# Summits7Beta_Sch.net
KiCad netlist of a schematic drawn in Altium Designer
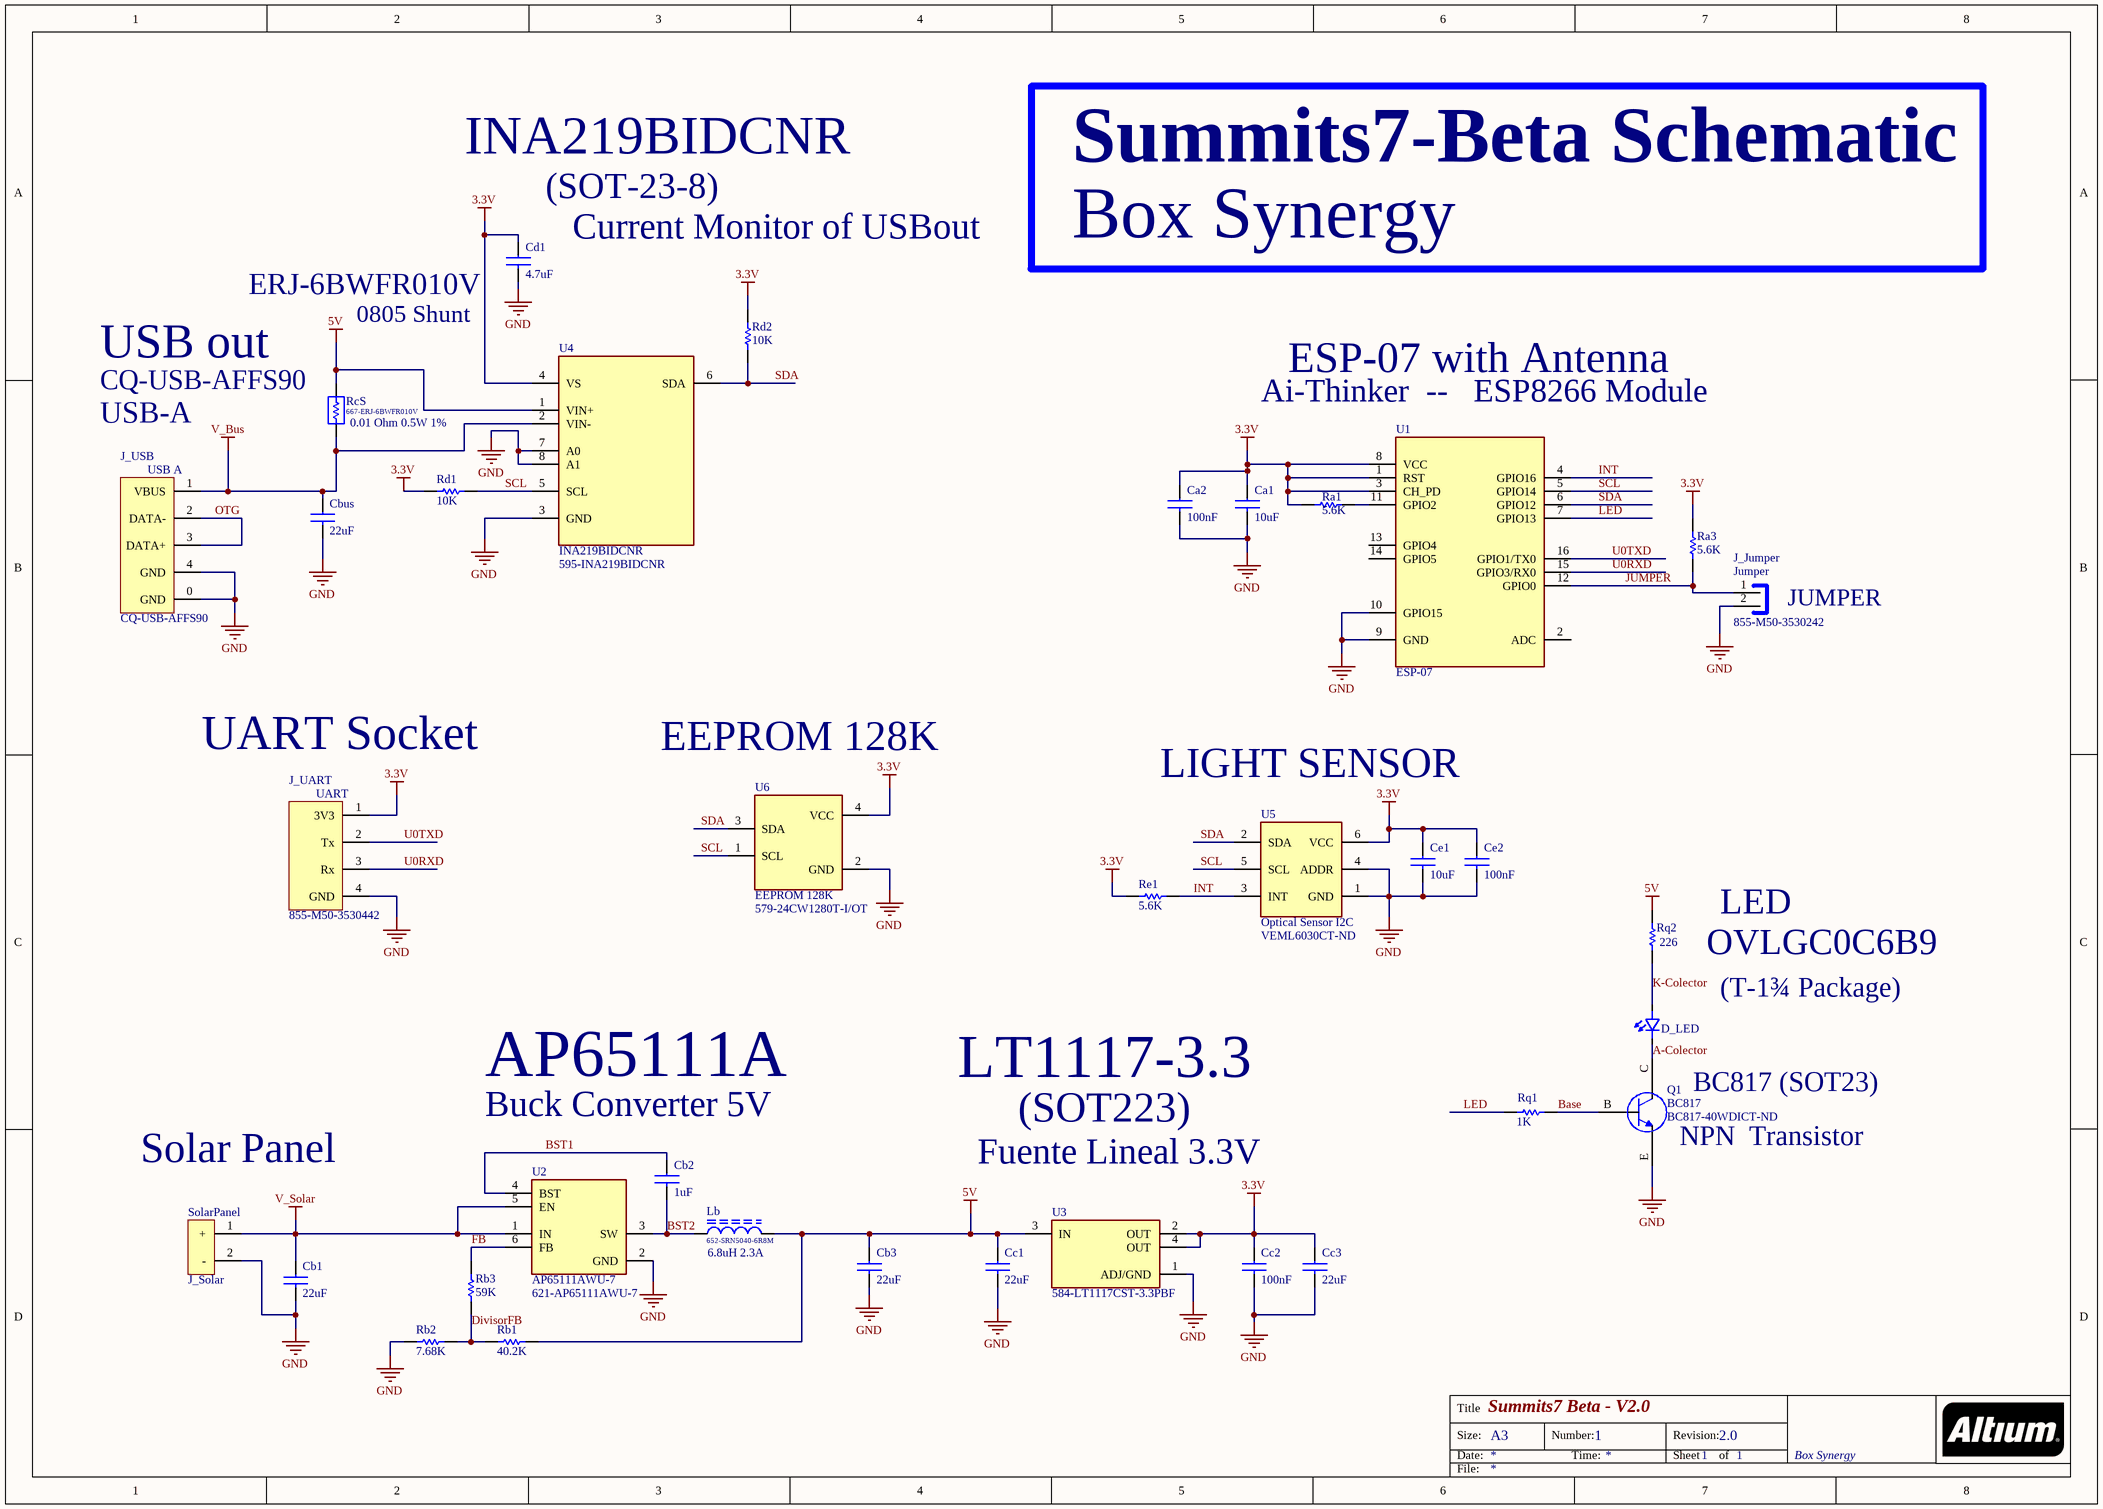
[diagram p0: Summits7Beta_Sch.SchDoc]

(export (version "E")
  (design (tool "Eeschema 10.0.6"))
  (components
    (comp (ref "Ca1")
      (value "10uF")
      (footprint "CAP_0603")
      (description "Capac Ceramic SMD")
      (libsource (lib "Summits7Beta_LIB_Pasivos_Sch") (part "Cap_0603_Ceramic"))
    )
    (comp (ref "Ca2")
      (value "100nF")
      (footprint "CAP_0603")
      (description "Capac Ceramic SMD")
      (libsource (lib "Summits7Beta_LIB_Pasivos_Sch") (part "Cap_0603_Ceramic"))
    )
    (comp (ref "Cb1")
      (value "22uF")
      (footprint "CAP_1210")
      (description "Capac Ceramic SMD")
      (libsource (lib "Summits7Beta_LIB_Pasivos_Sch") (part "Cap_1210_Ceramic"))
    )
    (comp (ref "Cb2")
      (value "1uF")
      (footprint "CAP_0603")
      (description "Capac Ceramic SMD")
      (libsource (lib "Summits7Beta_LIB_Pasivos_Sch") (part "Cap_0603_Ceramic"))
    )
    (comp (ref "Cb3")
      (value "22uF")
      (footprint "CAP_1210")
      (description "Capac Ceramic SMD")
      (libsource (lib "Summits7Beta_LIB_Pasivos_Sch") (part "Cap_1210_Ceramic"))
    )
    (comp (ref "Cbus")
      (value "22uF")
      (footprint "CAP_1210")
      (description "Capac Ceramic SMD")
      (libsource (lib "Summits7Beta_LIB_Pasivos_Sch") (part "Cap_1210_Ceramic"))
    )
    (comp (ref "Cc1")
      (value "22uF")
      (footprint "CAP_0603")
      (description "Capac Ceramic SMD")
      (libsource (lib "Summits7Beta_LIB_Pasivos_Sch") (part "Cap_0603_Ceramic"))
    )
    (comp (ref "Cc2")
      (value "100nF")
      (footprint "CAP_0603")
      (description "Capac Ceramic SMD")
      (libsource (lib "Summits7Beta_LIB_Pasivos_Sch") (part "Cap_0603_Ceramic"))
    )
    (comp (ref "Cc3")
      (value "22uF")
      (footprint "CAP_1210")
      (description "Capac Ceramic SMD")
      (libsource (lib "Summits7Beta_LIB_Pasivos_Sch") (part "Cap_1210_Ceramic"))
    )
    (comp (ref "Cd1")
      (value "4.7uF")
      (footprint "CAP_0603")
      (description "Capac Ceramic SMD")
      (libsource (lib "Summits7Beta_LIB_Pasivos_Sch") (part "Cap_0603_Ceramic"))
    )
    (comp (ref "Ce1")
      (value "10uF")
      (footprint "CAP_0603")
      (description "Capac Ceramic SMD")
      (libsource (lib "Summits7Beta_LIB_Pasivos_Sch") (part "Cap_0603_Ceramic"))
    )
    (comp (ref "Ce2")
      (value "100nF")
      (footprint "CAP_0603")
      (description "Capac Ceramic SMD")
      (libsource (lib "Summits7Beta_LIB_Pasivos_Sch") (part "Cap_0603_Ceramic"))
    )
    (comp (ref "D_LED")
      (value "OVLGC0C6B9")
      (footprint "LED")
      (description "LED Green-Blue 505nm")
      (fields (field (name "MF") "Broadcom Limited") (field (name "MP") "HSMW-C191"))
      (libsource (lib "Summits7Beta_LIB_Otros_Sch") (part "OVLGC0C6B9"))
    )
    (comp (ref "J_Jumper")
      (value "M50-3530242")
      (footprint "JUMPER-1.27 mm")
      (description "1.27mm Pin Header 2x1")
      (fields (field (name "SUPPLIER PART NUMBER 1") "855-M50-3530242"))
      (libsource (lib "Summits7Beta_LIB_Conectores_Sch") (part "Jumper"))
    )
    (comp (ref "J_Solar")
      (value "Connx2_Panel")
      (footprint "PANEL_IN")
      (description "Conector del Panel")
      (libsource (lib "Summits7Beta_LIB_Conectores_Sch") (part "Connx2_Panel"))
    )
    (comp (ref "J_UART")
      (value "M50-3530442")
      (footprint "UART-1.27mm")
      (description "1.27mm Pin Header 4x1")
      (fields (field (name "SUPPLIER PART NUMBER 1") "855-M50-3530442"))
      (libsource (lib "Summits7Beta_LIB_Conectores_Sch") (part "Connx4_UART"))
    )
    (comp (ref "J_USB")
      (value "CQ-USB-AFFS90")
      (footprint "USB-A__IPX8")
      (description "Conector del USB   --   CQ-USB-AFFS90")
      (libsource (lib "Summits7Beta_LIB_Conectores_Sch") (part "USB-A 5V"))
    )
    (comp (ref "Lb")
      (value "6.8uH 2.3A")
      (footprint "Inductor_SRN5040")
      (description "Inductor_SRN5040")
      (fields (field (name "MF") "Vishay Dale") (field (name "SUPPLIER PART NUMBER 1") "652-SRN5040-6R8M"))
      (libsource (lib "Summits7Beta_LIB_Pasivos_Sch") (part "Ind_SRN5040"))
    )
    (comp (ref "Q1")
      (value "BC817")
      (footprint "Transistor_SOT23-3")
      (description "Transistor NPN. Leave 2.5mm height from PCB")
      (fields (field (name "SUPPLIER PART NUMBER 1") "BC817-40WDICT-ND"))
      (libsource (lib "Summits7Beta_LIB_Integrados_Sch") (part "BC817"))
    )
    (comp (ref "Ra1")
      (value "5.6K")
      (footprint "RES_0603")
      (description "Resistor SMD")
      (fields (field (name "PUBLISHER") "Altium Limited"))
      (libsource (lib "Summits7Beta_LIB_Pasivos_Sch") (part "Res_0603"))
    )
    (comp (ref "Ra3")
      (value "5.6K")
      (footprint "RES_0603")
      (description "Resistor SMD")
      (fields (field (name "PUBLISHER") "Altium Limited"))
      (libsource (lib "Summits7Beta_LIB_Pasivos_Sch") (part "Res_0603"))
    )
    (comp (ref "Rb1")
      (value "40.2K")
      (footprint "RES_0603")
      (description "Resistor SMD")
      (fields (field (name "PUBLISHER") "Altium Limited"))
      (libsource (lib "Summits7Beta_LIB_Pasivos_Sch") (part "Res_0603"))
    )
    (comp (ref "Rb2")
      (value "7.68K")
      (footprint "RES_0603")
      (description "Resistor SMD")
      (fields (field (name "PUBLISHER") "Altium Limited"))
      (libsource (lib "Summits7Beta_LIB_Pasivos_Sch") (part "Res_0603"))
    )
    (comp (ref "Rb3")
      (value "59K")
      (footprint "RES_0603")
      (description "Resistor SMD")
      (fields (field (name "PUBLISHER") "Altium Limited"))
      (libsource (lib "Summits7Beta_LIB_Pasivos_Sch") (part "Res_0603"))
    )
    (comp (ref "RcS")
      (value "0.01 Ohm 0.5W 1%")
      (footprint "RES-SHUNT-0805")
      (description "Shunt")
      (fields
        (field (name "SUPPLIER PART NUMBER 1") "667-ERJ-6BWFR010V")
        (field (name "PUBLISHER") "Altium Limited")
      )
      (libsource (lib "Summits7Beta_LIB_Pasivos_Sch") (part "Shunt_0805"))
    )
    (comp (ref "Rd1")
      (value "10K")
      (footprint "RES_0603")
      (description "Resistor SMD")
      (fields (field (name "PUBLISHER") "Altium Limited"))
      (libsource (lib "Summits7Beta_LIB_Pasivos_Sch") (part "Res_0603"))
    )
    (comp (ref "Rd2")
      (value "10K")
      (footprint "RES_0603")
      (description "Resistor SMD")
      (fields (field (name "PUBLISHER") "Altium Limited"))
      (libsource (lib "Summits7Beta_LIB_Pasivos_Sch") (part "Res_0603"))
    )
    (comp (ref "Re1")
      (value "5.6K")
      (footprint "RES_0603")
      (description "Resistor SMD")
      (fields (field (name "PUBLISHER") "Altium Limited"))
      (libsource (lib "Summits7Beta_LIB_Pasivos_Sch") (part "Res_0603"))
    )
    (comp (ref "Rq1")
      (value "1K")
      (footprint "RES_0603")
      (description "Resistor SMD")
      (fields (field (name "PUBLISHER") "Altium Limited"))
      (libsource (lib "Summits7Beta_LIB_Pasivos_Sch") (part "Res_0603"))
    )
    (comp (ref "Rq2")
      (value "226")
      (footprint "RES_0603")
      (description "Resistor SMD")
      (fields (field (name "PUBLISHER") "Altium Limited"))
      (libsource (lib "Summits7Beta_LIB_Pasivos_Sch") (part "Res_0603"))
    )
    (comp (ref "U1")
      (value "ESP-07")
      (footprint "ESP-07")
      (description "ESP07 Module with Antenna Ai-Thinker")
      (fields (field (name "MP") "AP65111AWU-7") (field (name "MF") "Diodes Inc."))
      (libsource (lib "Summits7Beta_LIB_Integrados_Sch") (part "ESP-07"))
    )
    (comp (ref "U2")
      (value "AP65111AWU-7")
      (footprint "AP65111A-SOT23-6")
      (description "Buck Switching Regulator IC Positive Adjustable 0.8V 1 Output 1.5A SOT-23-6 Thin, TSOT-23-6")
      (fields (field (name "MF") "Diodes Inc.") (field (name "SUPPLIER PART NUMBER 1") "621-AP65111AWU-7"))
      (libsource (lib "Summits7Beta_LIB_Integrados_Sch") (part "AP65111AWU-7"))
    )
    (comp (ref "U3")
      (value "LT1117IST-3.3")
      (footprint "LT1117IST-3.3_SOT-223")
      (description "LDO Regulator Pos 3.3V 0.8A Automotive 4-Pin_3+Tab_ SOT-223 Tube")
      (fields
        (field (name "MP") "LT1117IST-5#PBF")
        (field (name "MF") "Analog Devices")
        (field (name "SUPPLIER PART NUMBER 1") "584-LT1117CST-3.3PBF")
      )
      (libsource (lib "Summits7Beta_LIB_Integrados_Sch") (part "LT1117IST-3.3"))
    )
    (comp (ref "U4")
      (value "INA219BIDCNR")
      (footprint "INA219B SOT23")
      (description "Current Monitor Regulator High-Side 10mA SOT-23-8")
      (fields
        (field (name "DIGI-KEY_PART_NUMBER") "296-46420-1-ND")
        (field (name "MF") "Texas Instruments")
        (field (name "SUPPLIER PART NUMBER 1") "595-INA219BIDCNR")
      )
      (libsource (lib "Summits7Beta_LIB_Integrados_Sch") (part "INA219BIDCNR"))
    )
    (comp (ref "U5")
      (value "Optical Sensor I2C")
      (footprint "VEML6030")
      (description "Optical Ambiental Light Sensor I2C with Interrupt")
      (fields (field (name "SUPPLIER PART NUMBER 1") "VEML6030CT-ND"))
      (libsource (lib "Summits7Beta_LIB_Integrados_Sch") (part "VEML6030"))
    )
    (comp (ref "U6")
      (value "EEPROM 128K")
      (footprint "24CW128")
      (fields (field (name "SUPPLIER PART NUMBER 1") "579-24CW1280T-I/OT"))
      (libsource (lib "Summits7Beta_LIB_Integrados_Sch") (part "24CW1280T-I/OT"))
    )
  )
  (nets
    (net (code "1") (name "/A-Colector") (class "Default")
      (node (ref "D_LED") (pin "1") (pinfunction "K_1") (pintype "passive"))
      (node (ref "Q1") (pin "C") (pinfunction "C_C") (pintype "passive"))
    )
    (net (code "2") (name "/BST1") (class "Default")
      (node (ref "Cb2") (pin "1") (pinfunction "1_1") (pintype "passive"))
      (node (ref "U2") (pin "4") (pinfunction "BST_4") (pintype "passive"))
    )
    (net (code "3") (name "/BST2") (class "Default")
      (node (ref "Cb2") (pin "2") (pinfunction "2_2") (pintype "passive"))
      (node (ref "Lb") (pin "2") (pinfunction "2_2") (pintype "passive"))
      (node (ref "U2") (pin "3") (pinfunction "SW_3") (pintype "passive"))
    )
    (net (code "4") (name "/Base") (class "Default")
      (node (ref "Q1") (pin "B") (pinfunction "B_B") (pintype "passive"))
      (node (ref "Rq1") (pin "1") (pinfunction "1_1") (pintype "passive"))
    )
    (net (code "5") (name "/DivisorFB") (class "Default")
      (node (ref "Rb1") (pin "2") (pinfunction "2_2") (pintype "passive"))
      (node (ref "Rb2") (pin "1") (pinfunction "1_1") (pintype "passive"))
      (node (ref "Rb3") (pin "2") (pinfunction "2_2") (pintype "passive"))
    )
    (net (code "6") (name "/FB") (class "Default")
      (node (ref "Rb3") (pin "1") (pinfunction "1_1") (pintype "passive"))
      (node (ref "U2") (pin "6") (pinfunction "FB_6") (pintype "passive"))
    )
    (net (code "7") (name "/INT") (class "Default")
      (node (ref "Re1") (pin "2") (pinfunction "2_2") (pintype "passive"))
      (node (ref "U1") (pin "4") (pinfunction "GPIO16_4") (pintype "passive"))
      (node (ref "U5") (pin "3") (pinfunction "INT_3") (pintype "passive"))
    )
    (net (code "8") (name "/JUMPER") (class "Default")
      (node (ref "J_Jumper") (pin "1") (pinfunction "1_1") (pintype "passive"))
      (node (ref "Ra3") (pin "2") (pinfunction "2_2") (pintype "passive"))
      (node (ref "U1") (pin "12") (pinfunction "GPIO0_12") (pintype "passive"))
    )
    (net (code "9") (name "/K-Colector") (class "Default")
      (node (ref "D_LED") (pin "2") (pinfunction "A_2") (pintype "passive"))
      (node (ref "Rq2") (pin "2") (pinfunction "2_2") (pintype "passive"))
    )
    (net (code "10") (name "/LED") (class "Default")
      (node (ref "Rq1") (pin "2") (pinfunction "2_2") (pintype "passive"))
      (node (ref "U1") (pin "7") (pinfunction "GPIO13_7") (pintype "passive"))
    )
    (net (code "11") (name "/OTG") (class "Default")
      (node (ref "J_USB") (pin "2") (pinfunction "DATA-_2") (pintype "passive"))
      (node (ref "J_USB") (pin "3") (pinfunction "DATA+_3") (pintype "passive"))
    )
    (net (code "12") (name "/SCL") (class "Default")
      (node (ref "Rd1") (pin "2") (pinfunction "2_2") (pintype "passive"))
      (node (ref "U1") (pin "5") (pinfunction "GPIO14_5") (pintype "passive"))
      (node (ref "U4") (pin "5") (pinfunction "SCL_5") (pintype "passive"))
      (node (ref "U5") (pin "5") (pinfunction "SCL_5") (pintype "passive"))
      (node (ref "U6") (pin "1") (pinfunction "SCL_1") (pintype "passive"))
    )
    (net (code "13") (name "/SDA") (class "Default")
      (node (ref "Rd2") (pin "2") (pinfunction "2_2") (pintype "passive"))
      (node (ref "U1") (pin "6") (pinfunction "GPIO12_6") (pintype "passive"))
      (node (ref "U4") (pin "6") (pinfunction "SDA_6") (pintype "passive"))
      (node (ref "U5") (pin "2") (pinfunction "SDA_2") (pintype "passive"))
      (node (ref "U6") (pin "3") (pinfunction "SDA_3") (pintype "passive"))
    )
    (net (code "14") (name "/U0RXD") (class "Default")
      (node (ref "J_UART") (pin "3") (pinfunction "Rx_3") (pintype "passive"))
      (node (ref "U1") (pin "15") (pinfunction "GPIO3/RX0_15") (pintype "passive"))
    )
    (net (code "15") (name "/U0TXD") (class "Default")
      (node (ref "J_UART") (pin "2") (pinfunction "Tx_2") (pintype "passive"))
      (node (ref "U1") (pin "16") (pinfunction "GPIO1/TX0_16") (pintype "passive"))
    )
    (net (code "16") (name "3.3V") (class "Default")
      (node (ref "Ca1") (pin "1") (pinfunction "1_1") (pintype "passive"))
      (node (ref "Ca2") (pin "1") (pinfunction "1_1") (pintype "passive"))
      (node (ref "Cc2") (pin "1") (pinfunction "1_1") (pintype "passive"))
      (node (ref "Cc3") (pin "1") (pinfunction "1_1") (pintype "passive"))
      (node (ref "Cd1") (pin "1") (pinfunction "1_1") (pintype "passive"))
      (node (ref "Ce1") (pin "1") (pinfunction "1_1") (pintype "passive"))
      (node (ref "Ce2") (pin "1") (pinfunction "1_1") (pintype "passive"))
      (node (ref "J_UART") (pin "1") (pinfunction "3V3_1") (pintype "passive"))
      (node (ref "Ra1") (pin "2") (pinfunction "2_2") (pintype "passive"))
      (node (ref "Ra3") (pin "1") (pinfunction "1_1") (pintype "passive"))
      (node (ref "Rd1") (pin "1") (pinfunction "1_1") (pintype "passive"))
      (node (ref "Rd2") (pin "1") (pinfunction "1_1") (pintype "passive"))
      (node (ref "Re1") (pin "1") (pinfunction "1_1") (pintype "passive"))
      (node (ref "U1") (pin "1") (pinfunction "RST_1") (pintype "passive"))
      (node (ref "U1") (pin "3") (pinfunction "CH_PD_3") (pintype "passive"))
      (node (ref "U1") (pin "8") (pinfunction "VCC_8") (pintype "passive"))
      (node (ref "U3") (pin "2") (pinfunction "OUT_2") (pintype "passive"))
      (node (ref "U3") (pin "4") (pinfunction "OUT_4") (pintype "passive"))
      (node (ref "U4") (pin "4") (pinfunction "VS_4") (pintype "power_in"))
      (node (ref "U5") (pin "6") (pinfunction "VCC_6") (pintype "passive"))
      (node (ref "U6") (pin "4") (pinfunction "VCC_4") (pintype "passive"))
    )
    (net (code "17") (name "5V") (class "Default")
      (node (ref "Cb3") (pin "1") (pinfunction "1_1") (pintype "passive"))
      (node (ref "Cc1") (pin "1") (pinfunction "1_1") (pintype "passive"))
      (node (ref "Lb") (pin "1") (pinfunction "1_1") (pintype "passive"))
      (node (ref "Rb1") (pin "1") (pinfunction "1_1") (pintype "passive"))
      (node (ref "RcS") (pin "1") (pinfunction "1_1") (pintype "passive"))
      (node (ref "Rq2") (pin "1") (pinfunction "1_1") (pintype "passive"))
      (node (ref "U3") (pin "3") (pinfunction "IN_3") (pintype "passive"))
      (node (ref "U4") (pin "1") (pinfunction "VIN+_1") (pintype "passive"))
    )
    (net (code "18") (name "GND") (class "Default")
      (node (ref "Ca1") (pin "2") (pinfunction "2_2") (pintype "passive"))
      (node (ref "Ca2") (pin "2") (pinfunction "2_2") (pintype "passive"))
      (node (ref "Cb1") (pin "2") (pinfunction "2_2") (pintype "passive"))
      (node (ref "Cb3") (pin "2") (pinfunction "2_2") (pintype "passive"))
      (node (ref "Cbus") (pin "2") (pinfunction "2_2") (pintype "passive"))
      (node (ref "Cc1") (pin "2") (pinfunction "2_2") (pintype "passive"))
      (node (ref "Cc2") (pin "2") (pinfunction "2_2") (pintype "passive"))
      (node (ref "Cc3") (pin "2") (pinfunction "2_2") (pintype "passive"))
      (node (ref "Cd1") (pin "2") (pinfunction "2_2") (pintype "passive"))
      (node (ref "Ce1") (pin "2") (pinfunction "2_2") (pintype "passive"))
      (node (ref "Ce2") (pin "2") (pinfunction "2_2") (pintype "passive"))
      (node (ref "J_Jumper") (pin "2") (pinfunction "2_2") (pintype "passive"))
      (node (ref "J_Solar") (pin "2") (pinfunction "-_2") (pintype "passive"))
      (node (ref "J_UART") (pin "4") (pinfunction "GND_4") (pintype "passive"))
      (node (ref "J_USB") (pin "0") (pinfunction "GND_0") (pintype "passive"))
      (node (ref "J_USB") (pin "4") (pinfunction "GND_4") (pintype "passive"))
      (node (ref "Q1") (pin "E") (pinfunction "E_E") (pintype "passive"))
      (node (ref "Rb2") (pin "2") (pinfunction "2_2") (pintype "passive"))
      (node (ref "U1") (pin "10") (pinfunction "GPIO15_10") (pintype "passive"))
      (node (ref "U1") (pin "9") (pinfunction "GND_9") (pintype "passive"))
      (node (ref "U2") (pin "2") (pinfunction "GND_2") (pintype "passive"))
      (node (ref "U3") (pin "1") (pinfunction "ADJ/GND_1") (pintype "passive"))
      (node (ref "U4") (pin "3") (pinfunction "GND_3") (pintype "passive"))
      (node (ref "U4") (pin "7") (pinfunction "A0_7") (pintype "passive"))
      (node (ref "U4") (pin "8") (pinfunction "A1_8") (pintype "passive"))
      (node (ref "U5") (pin "1") (pinfunction "GND_1") (pintype "passive"))
      (node (ref "U5") (pin "4") (pinfunction "ADDR_4") (pintype "passive"))
      (node (ref "U6") (pin "2") (pinfunction "GND_2") (pintype "passive"))
    )
    (net (code "19") (name "Net-(U1-GPIO2)") (class "Default")
      (node (ref "Ra1") (pin "1") (pinfunction "1_1") (pintype "passive"))
      (node (ref "U1") (pin "11") (pinfunction "GPIO2_11") (pintype "passive"))
    )
    (net (code "20") (name "V_Bus") (class "Default")
      (node (ref "Cbus") (pin "1") (pinfunction "1_1") (pintype "passive"))
      (node (ref "J_USB") (pin "1") (pinfunction "VBUS_1") (pintype "power_in"))
      (node (ref "RcS") (pin "2") (pinfunction "2_2") (pintype "passive"))
      (node (ref "U4") (pin "2") (pinfunction "VIN-_2") (pintype "passive"))
    )
    (net (code "21") (name "V_Solar") (class "Default")
      (node (ref "Cb1") (pin "1") (pinfunction "1_1") (pintype "passive"))
      (node (ref "J_Solar") (pin "1") (pinfunction "+_1") (pintype "passive"))
      (node (ref "U2") (pin "1") (pinfunction "IN_1") (pintype "passive"))
      (node (ref "U2") (pin "5") (pinfunction "EN_5") (pintype "passive"))
    )
    (net (code "22") (name "unconnected-(U1-ADC-Pad2)") (class "Default")
      (node (ref "U1") (pin "2") (pinfunction "ADC_2") (pintype "passive"))
    )
    (net (code "23") (name "unconnected-(U1-GPIO4-Pad13)") (class "Default")
      (node (ref "U1") (pin "13") (pinfunction "GPIO4_13") (pintype "passive"))
    )
    (net (code "24") (name "unconnected-(U1-GPIO5-Pad14)") (class "Default")
      (node (ref "U1") (pin "14") (pinfunction "GPIO5_14") (pintype "passive"))
    )
  )
)
